# oresat-camera-card-usb-breakout-v0.net
KiCad netlist of a schematic drawn in EAGLE
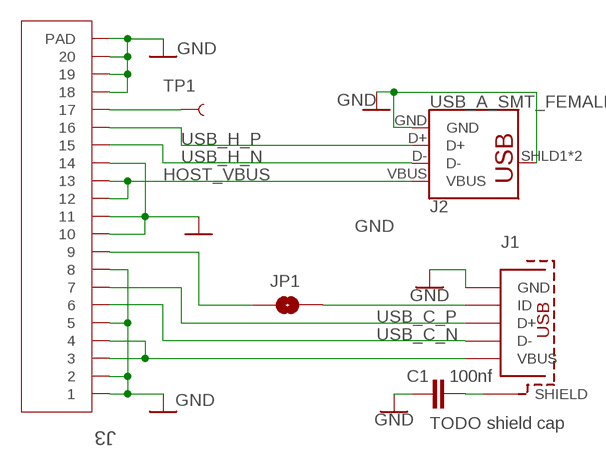
[diagram p0: schematic, sheet 1]

(export (version "E")
  (design (tool "Eeschema 10.0.6"))
  (components
    (comp (ref "C1")
      (value "100nf")
      (footprint "eagle-import:.0603-A")
      (libsource (lib "eagle-import") (part "C-EU0603-A"))
    )
    (comp (ref "J1")
      (value "MICRO-USB-SOCKET")
      (footprint "eagle-import:629105136821")
      (libsource (lib "eagle-import") (part "MICRO-USB-SOCKET"))
    )
    (comp (ref "J2")
      (value "USB_A_SMT_FEMALE")
      (footprint "eagle-import:USB-A-S-SILK-FEMALE")
      (libsource (lib "eagle-import") (part "USB_A_SMT_FEMALE"))
    )
    (comp (ref "J3")
      (value "2-1734592-0")
      (footprint "eagle-import:TE_2-1734592-0")
      (libsource (lib "eagle-import") (part "2-1734592-0"))
    )
    (comp (ref "JP1")
      (value "JUMPER-SMT_2_NO_SILK")
      (footprint "eagle-import:SMT-JUMPER_2_NO_SILK")
      (libsource (lib "eagle-import") (part "JUMPER-SMT_2_NO_SILK"))
    )
    (comp (ref "TP1")
      (value "TEST-POINTPOGO_PTH")
      (footprint "eagle-import:1X01_NO_SILK")
      (libsource (lib "eagle-import") (part "TEST-POINTPOGO_PTH"))
    )
  )
  (nets
    (net (code "1") (name "/HOST_VBUS") (class "Default")
      (node (ref "J2") (pin "VBUS") (pinfunction "VBUS_VBUS") (pintype "power_in"))
      (node (ref "J3") (pin "12") (pinfunction "12_12") (pintype "passive"))
      (node (ref "J3") (pin "13") (pinfunction "13_13") (pintype "passive"))
    )
    (net (code "2") (name "/USB_C_N") (class "Default")
      (node (ref "J1") (pin "2") (pinfunction "D-_2") (pintype "passive"))
      (node (ref "J3") (pin "6") (pinfunction "6_6") (pintype "passive"))
    )
    (net (code "3") (name "/USB_C_P") (class "Default")
      (node (ref "J1") (pin "3") (pinfunction "D+_3") (pintype "passive"))
      (node (ref "J3") (pin "7") (pinfunction "7_7") (pintype "passive"))
    )
    (net (code "4") (name "/USB_H_N") (class "Default")
      (node (ref "J2") (pin "D-") (pinfunction "D-_D-") (pintype "bidirectional"))
      (node (ref "J3") (pin "15") (pinfunction "15_15") (pintype "passive"))
    )
    (net (code "5") (name "/USB_H_P") (class "Default")
      (node (ref "J2") (pin "D+") (pinfunction "D+_D+") (pintype "bidirectional"))
      (node (ref "J3") (pin "16") (pinfunction "16_16") (pintype "passive"))
    )
    (net (code "6") (name "GND") (class "Default")
      (node (ref "C1") (pin "1") (pinfunction "1_1") (pintype "passive"))
      (node (ref "J1") (pin "5") (pinfunction "GND_5") (pintype "passive"))
      (node (ref "J2") (pin "GND") (pinfunction "GND_GND") (pintype "power_in"))
      (node (ref "J2") (pin "SHLD1") (pinfunction "SHIELD_SHLD1") (pintype "bidirectional"))
      (node (ref "J2") (pin "SHLD2") (pinfunction "SHIELD_SHLD2") (pintype "bidirectional"))
      (node (ref "J3") (pin "1") (pinfunction "1_1") (pintype "passive"))
      (node (ref "J3") (pin "10") (pinfunction "10_10") (pintype "passive"))
      (node (ref "J3") (pin "11") (pinfunction "11_11") (pintype "passive"))
      (node (ref "J3") (pin "14") (pinfunction "14_14") (pintype "passive"))
      (node (ref "J3") (pin "18") (pinfunction "18_18") (pintype "passive"))
      (node (ref "J3") (pin "19") (pinfunction "19_19") (pintype "passive"))
      (node (ref "J3") (pin "2") (pinfunction "2_2") (pintype "passive"))
      (node (ref "J3") (pin "20") (pinfunction "20_20") (pintype "passive"))
      (node (ref "J3") (pin "5") (pinfunction "5_5") (pintype "passive"))
      (node (ref "J3") (pin "8") (pinfunction "8_8") (pintype "passive"))
      (node (ref "J3") (pin "S1") (pinfunction "PAD_S1") (pintype "bidirectional"))
      (node (ref "J3") (pin "S2") (pinfunction "PAD_S2") (pintype "bidirectional"))
    )
    (net (code "7") (name "Net-(C1-Pad2)") (class "Default")
      (node (ref "C1") (pin "2") (pinfunction "2_2") (pintype "passive"))
      (node (ref "J1") (pin "SHELL") (pinfunction "SHIELD_SHELL") (pintype "passive"))
      (node (ref "J1") (pin "SHELL1") (pinfunction "SHIELD_SHELL1") (pintype "passive"))
      (node (ref "J1") (pin "SHELL2") (pinfunction "SHIELD_SHELL2") (pintype "passive"))
      (node (ref "J1") (pin "SHELL3") (pinfunction "SHIELD_SHELL3") (pintype "passive"))
    )
    (net (code "8") (name "Net-(J1-ID)") (class "Default")
      (node (ref "J1") (pin "4") (pinfunction "ID_4") (pintype "passive"))
      (node (ref "JP1") (pin "2") (pinfunction "2_2") (pintype "passive"))
    )
    (net (code "9") (name "Net-(J1-VBUS)") (class "Default")
      (node (ref "J1") (pin "1") (pinfunction "VBUS_1") (pintype "passive"))
      (node (ref "J3") (pin "3") (pinfunction "3_3") (pintype "passive"))
      (node (ref "J3") (pin "4") (pinfunction "4_4") (pintype "passive"))
    )
    (net (code "10") (name "Net-(J3-Pad9)") (class "Default")
      (node (ref "J3") (pin "9") (pinfunction "9_9") (pintype "passive"))
      (node (ref "JP1") (pin "1") (pinfunction "1_1") (pintype "passive"))
    )
    (net (code "11") (name "Net-(J3-Pad17)") (class "Default")
      (node (ref "J3") (pin "17") (pinfunction "17_17") (pintype "passive"))
      (node (ref "TP1") (pin "1") (pinfunction "1_1") (pintype "bidirectional"))
    )
  )
)
